# triggerbox.net
KiCad netlist of a schematic drawn in Altium Designer
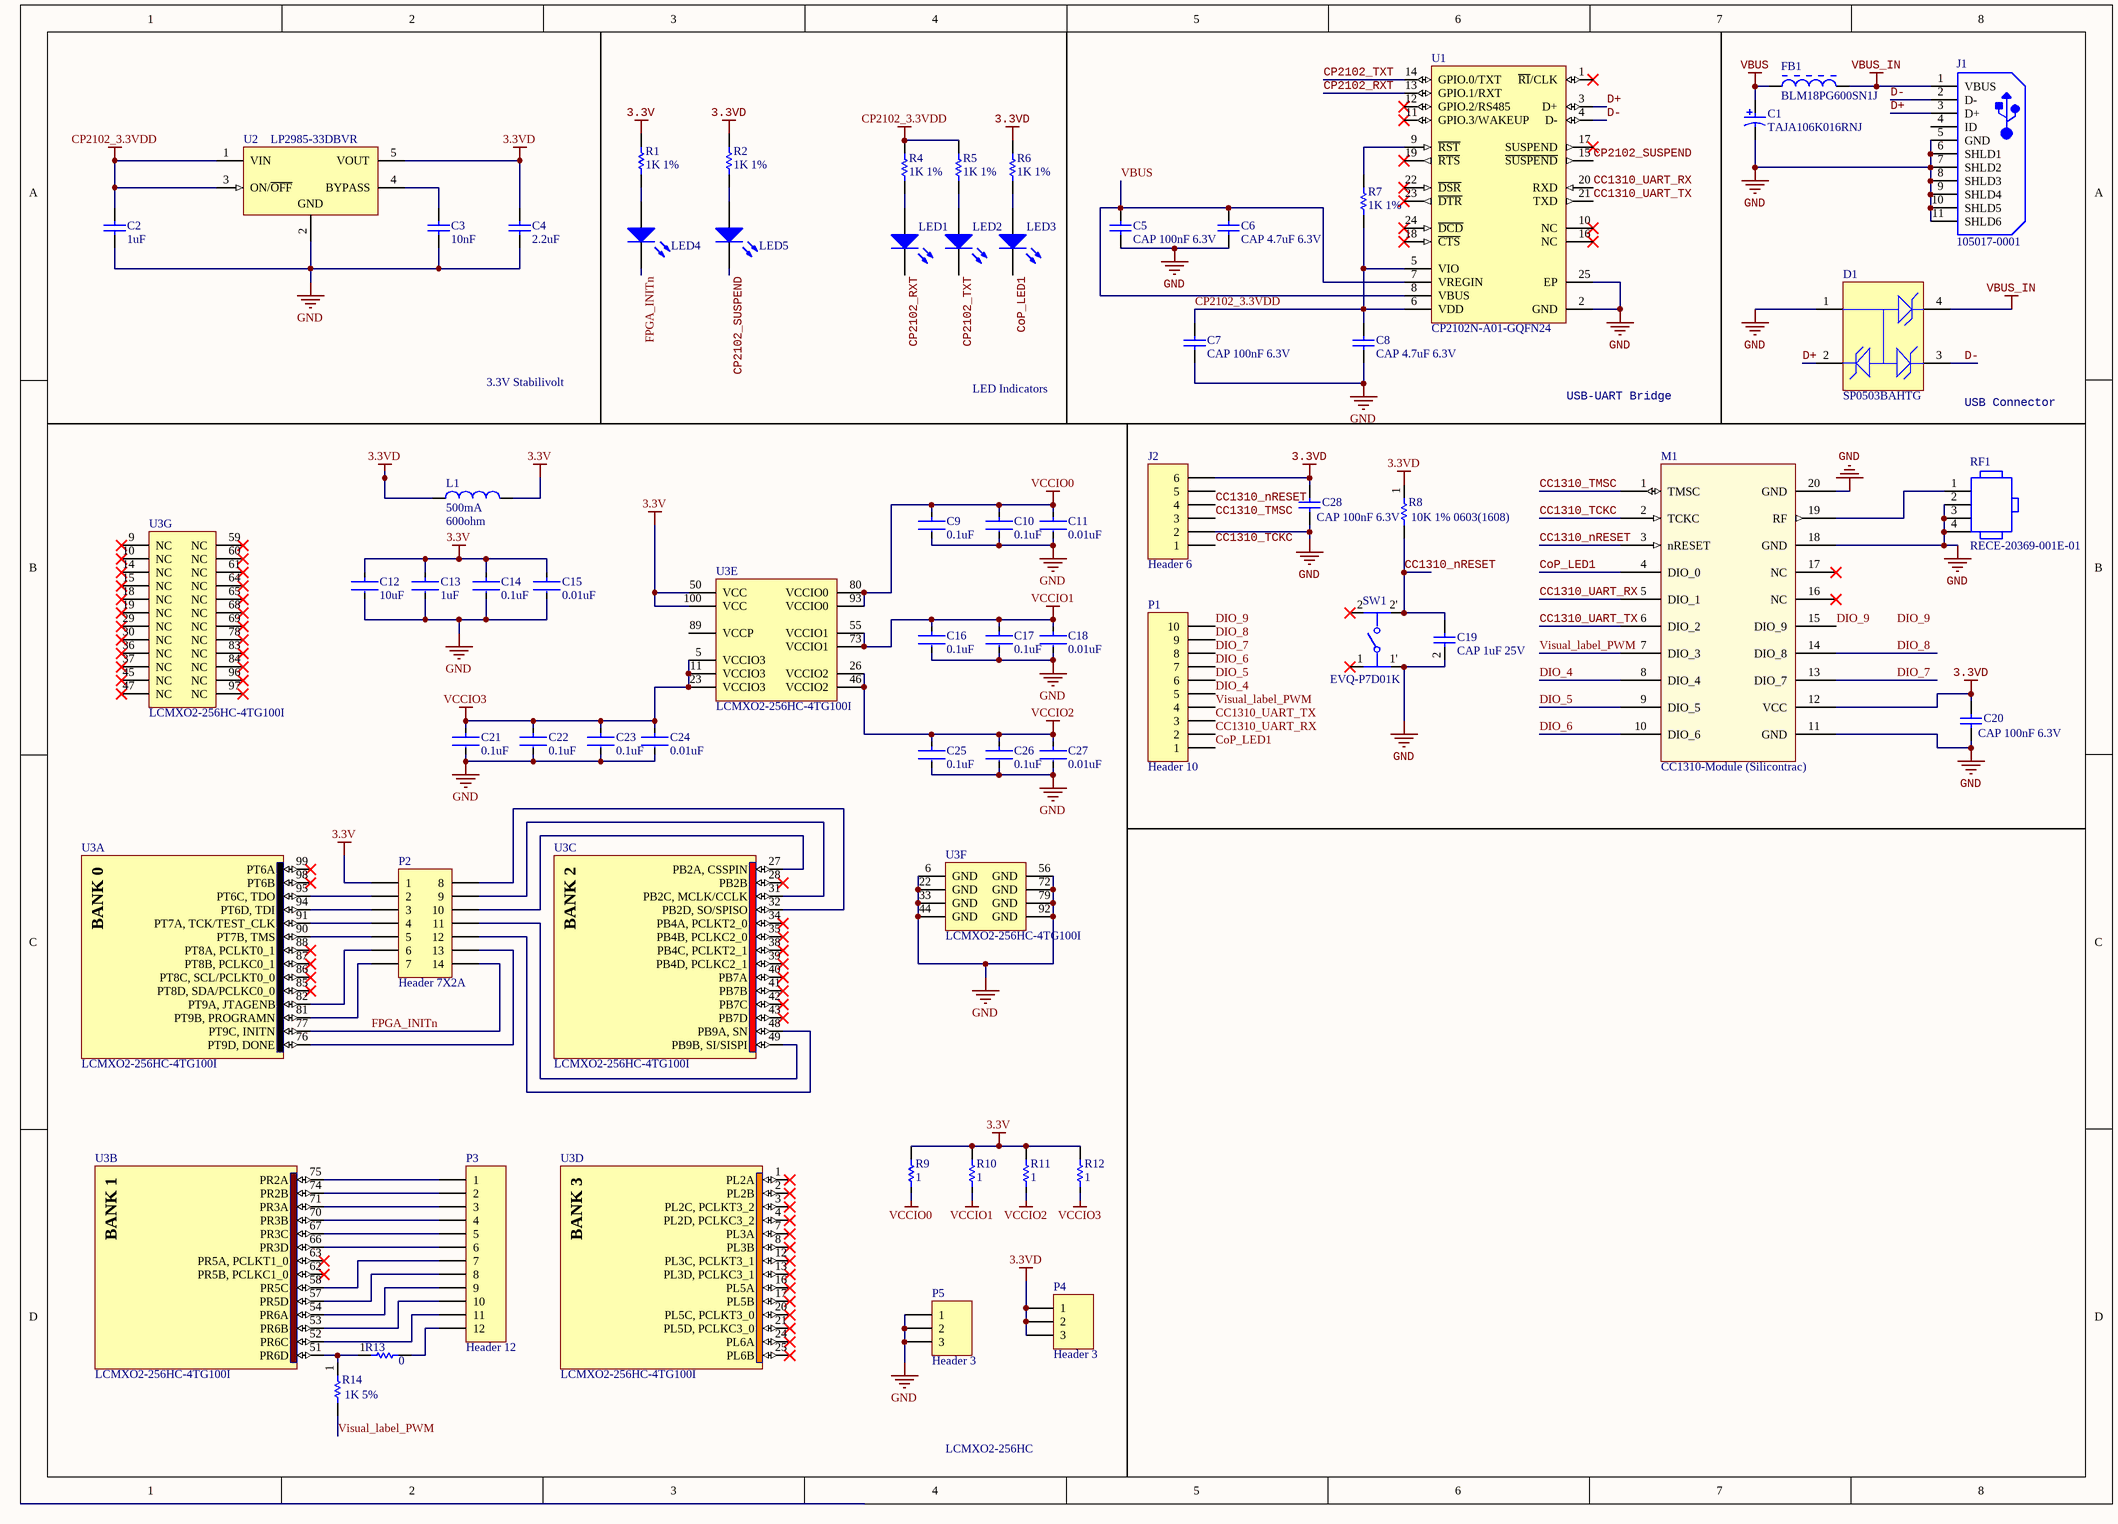
[diagram p0: triggerbox.SchDoc]

(export (version "E")
  (design (tool "Eeschema 10.0.6"))
  (components
    (comp (ref "C1")
      (value "TAJA106K016RNJ")
      (footprint "CAPMP3217X18-T_V")
      (description "Standard Tantalum, 10 uF, +/- 10%, 16 V, -55 to 125 degC, 2-Pin SMD (1206), RoHS, Tape and Reel")
      (libsource (lib "Altium Content Vault") (part "CAP-P-2"))
    )
    (comp (ref "C2")
      (value "1uF")
      (footprint "CAPC0603(1608)55_N")
      (description "CAP 4.7uF 10V ±20% 0603 (1608 Metric) Thickness 0.55mm SMD")
      (fields (field (name "TOLERANCE") "Â±20%"))
      (libsource (lib "Altium Content Vault") (part "CAP"))
    )
    (comp (ref "C3")
      (value "10nF")
      (footprint "CAPC0603(1608)55_N")
      (description "CAP 4.7uF 10V ±20% 0603 (1608 Metric) Thickness 0.55mm SMD")
      (fields (field (name "TOLERANCE") "Â±20%"))
      (libsource (lib "Altium Content Vault") (part "CAP"))
    )
    (comp (ref "C4")
      (value "2.2uF")
      (footprint "CAPC0603(1608)55_N")
      (description "CAP 4.7uF 10V ±20% 0603 (1608 Metric) Thickness 0.55mm SMD")
      (fields (field (name "TOLERANCE") "Â±20%"))
      (libsource (lib "Altium Content Vault") (part "CAP"))
    )
    (comp (ref "C5")
      (value "CAP 100nF 6.3V")
      (footprint "CAPC0603(1608)100_N")
      (description "CAP 100nF 6.3V ±5% 0603 (1608 Metric) Thickness 1mm SMD")
      (fields (field (name "TOLERANCE") "Â±5%"))
      (libsource (lib "Altium Content Vault") (part "CAP"))
    )
    (comp (ref "C6")
      (value "CAP 4.7uF 6.3V")
      (footprint "CAPC0603(1608)100_N")
      (description "CAP 4.7uF 6.3V ±20% 0603 (1608 Metric) Thickness 1mm SMD")
      (fields (field (name "TOLERANCE") "Â±20%"))
      (libsource (lib "Altium Content Vault") (part "CAP"))
    )
    (comp (ref "C7")
      (value "CAP 100nF 6.3V")
      (footprint "CAPC0603(1608)100_N")
      (description "CAP 100nF 6.3V ±5% 0603 (1608 Metric) Thickness 1mm SMD")
      (fields (field (name "TOLERANCE") "Â±5%"))
      (libsource (lib "Altium Content Vault") (part "CAP"))
    )
    (comp (ref "C8")
      (value "CAP 4.7uF 6.3V")
      (footprint "CAPC0603(1608)100_N")
      (description "CAP 4.7uF 6.3V ±20% 0603 (1608 Metric) Thickness 1mm SMD")
      (fields (field (name "TOLERANCE") "Â±20%"))
      (libsource (lib "Altium Content Vault") (part "CAP"))
    )
    (comp (ref "C9")
      (value "0.1uF")
      (footprint "FP-GRM155-0_05-IPC_A")
      (description "CAP CER 0.1UF 10V X5R 0402")
      (fields (field (name "VOLTAGE") "10V") (field (name "TOLERANCE") "10%"))
      (libsource (lib "Altium Content Vault") (part "02cd4be3c70576c341d710602a673aa"))
    )
    (comp (ref "C10")
      (value "0.1uF")
      (footprint "FP-GRM155-0_05-IPC_A")
      (description "CAP CER 0.1UF 10V X5R 0402")
      (fields (field (name "VOLTAGE") "10V") (field (name "TOLERANCE") "10%"))
      (libsource (lib "Altium Content Vault") (part "02cd4be3c70576c341d710602a673aa"))
    )
    (comp (ref "C11")
      (value "0.01uF")
      (footprint "FP-GRM155-0_05-IPC_A")
      (description "CAP CER 0.01UF 10V X5R 0402")
      (fields (field (name "VOLTAGE") "10V") (field (name "TOLERANCE") "10%"))
      (libsource (lib "Altium Content Vault") (part "02cd4be3c70576c341d710602a673aa"))
    )
    (comp (ref "C12")
      (value "10uF")
      (footprint "FP-GRM155-0_05-IPC_A")
      (description "CAP CER 0.1UF 10V X5R 0402")
      (fields (field (name "VOLTAGE") "10V") (field (name "TOLERANCE") "10%"))
      (libsource (lib "Altium Content Vault") (part "02cd4be3c70576c341d710602a673aa"))
    )
    (comp (ref "C13")
      (value "1uF")
      (footprint "FP-GRM155-0_05-IPC_A")
      (description "CAP CER 0.1UF 10V X5R 0402")
      (fields (field (name "VOLTAGE") "10V") (field (name "TOLERANCE") "10%"))
      (libsource (lib "Altium Content Vault") (part "02cd4be3c70576c341d710602a673aa"))
    )
    (comp (ref "C14")
      (value "0.1uF")
      (footprint "FP-GRM155-0_05-IPC_A")
      (description "CAP CER 0.1UF 10V X5R 0402")
      (fields (field (name "VOLTAGE") "10V") (field (name "TOLERANCE") "10%"))
      (libsource (lib "Altium Content Vault") (part "02cd4be3c70576c341d710602a673aa"))
    )
    (comp (ref "C15")
      (value "0.01uF")
      (footprint "FP-GRM155-0_05-IPC_A")
      (description "CAP CER 0.1UF 10V X5R 0402")
      (fields (field (name "VOLTAGE") "10V") (field (name "TOLERANCE") "10%"))
      (libsource (lib "Altium Content Vault") (part "02cd4be3c70576c341d710602a673aa"))
    )
    (comp (ref "C16")
      (value "0.1uF")
      (footprint "FP-GRM155-0_05-IPC_A")
      (description "CAP CER 0.1UF 10V X5R 0402")
      (fields (field (name "VOLTAGE") "10V") (field (name "TOLERANCE") "10%"))
      (libsource (lib "Altium Content Vault") (part "02cd4be3c70576c341d710602a673aa"))
    )
    (comp (ref "C17")
      (value "0.1uF")
      (footprint "FP-GRM155-0_05-IPC_A")
      (description "CAP CER 0.1UF 10V X5R 0402")
      (fields (field (name "VOLTAGE") "10V") (field (name "TOLERANCE") "10%"))
      (libsource (lib "Altium Content Vault") (part "02cd4be3c70576c341d710602a673aa"))
    )
    (comp (ref "C18")
      (value "0.01uF")
      (footprint "FP-GRM155-0_05-IPC_A")
      (description "CAP CER 0.01UF 10V X5R 0402")
      (fields (field (name "VOLTAGE") "10V") (field (name "TOLERANCE") "10%"))
      (libsource (lib "Altium Content Vault") (part "02cd4be3c70576c341d710602a673aa"))
    )
    (comp (ref "C19")
      (value "CAP 1uF 25V")
      (footprint "CAPC0603(1608)100_N")
      (description "CAP 1uF 25V ±20% 0603 (1608 Metric) Thickness 1mm SMD")
      (fields (field (name "TOLERANCE") "Â±20%"))
      (libsource (lib "") (part "CAP_1"))
    )
    (comp (ref "C20")
      (value "CAP 100nF 6.3V")
      (footprint "CAPC0603(1608)100_N")
      (description "CAP 100nF 6.3V ±10% 0603 (1608 Metric) Thickness 1mm SMD")
      (fields (field (name "TOLERANCE") "Â±10%"))
      (libsource (lib "Altium Content Vault") (part "CAP"))
    )
    (comp (ref "C21")
      (value "0.1uF")
      (footprint "FP-GRM155-0_05-IPC_A")
      (description "CAP CER 0.1UF 10V X5R 0402")
      (fields (field (name "VOLTAGE") "10V") (field (name "TOLERANCE") "10%"))
      (libsource (lib "Altium Content Vault") (part "02cd4be3c70576c341d710602a673aa"))
    )
    (comp (ref "C22")
      (value "0.1uF")
      (footprint "FP-GRM155-0_05-IPC_A")
      (description "CAP CER 0.1UF 10V X5R 0402")
      (fields (field (name "VOLTAGE") "10V") (field (name "TOLERANCE") "10%"))
      (libsource (lib "Altium Content Vault") (part "02cd4be3c70576c341d710602a673aa"))
    )
    (comp (ref "C23")
      (value "0.1uF")
      (footprint "FP-GRM155-0_05-IPC_A")
      (description "CAP CER 0.1UF 10V X5R 0402")
      (fields (field (name "VOLTAGE") "10V") (field (name "TOLERANCE") "10%"))
      (libsource (lib "Altium Content Vault") (part "02cd4be3c70576c341d710602a673aa"))
    )
    (comp (ref "C24")
      (value "0.01uF")
      (footprint "FP-GRM155-0_05-IPC_A")
      (description "CAP CER 0.01UF 10V X5R 0402")
      (fields (field (name "VOLTAGE") "10V") (field (name "TOLERANCE") "10%"))
      (libsource (lib "Altium Content Vault") (part "02cd4be3c70576c341d710602a673aa"))
    )
    (comp (ref "C25")
      (value "0.1uF")
      (footprint "FP-GRM155-0_05-IPC_A")
      (description "CAP CER 0.1UF 10V X5R 0402")
      (fields (field (name "VOLTAGE") "10V") (field (name "TOLERANCE") "10%"))
      (libsource (lib "Altium Content Vault") (part "02cd4be3c70576c341d710602a673aa"))
    )
    (comp (ref "C26")
      (value "0.1uF")
      (footprint "FP-GRM155-0_05-IPC_A")
      (description "CAP CER 0.1UF 10V X5R 0402")
      (fields (field (name "VOLTAGE") "10V") (field (name "TOLERANCE") "10%"))
      (libsource (lib "Altium Content Vault") (part "02cd4be3c70576c341d710602a673aa"))
    )
    (comp (ref "C27")
      (value "0.01uF")
      (footprint "FP-GRM155-0_05-IPC_A")
      (description "CAP CER 0.01UF 10V X5R 0402")
      (fields (field (name "VOLTAGE") "10V") (field (name "TOLERANCE") "10%"))
      (libsource (lib "Altium Content Vault") (part "02cd4be3c70576c341d710602a673aa"))
    )
    (comp (ref "C28")
      (value "CAP 100nF 6.3V")
      (footprint "CAPC0603(1608)100_N")
      (description "CAP 100nF 6.3V ±10% 0603 (1608 Metric) Thickness 1mm SMD")
      (fields (field (name "TOLERANCE") "Â±10%"))
      (libsource (lib "Altium Content Vault") (part "CAP"))
    )
    (comp (ref "D1")
      (value "SP0503BAHTG")
      (footprint "LFUS-SOT143-4_V")
      (description "TVS Diode Array, 30 pF, 30 KV, -40 to 85 degC, 4-Pin SOT143, RoHS, Tape and Reel")
      (fields (field (name "MANUFACTURER") "Littelfuse"))
      (libsource (lib "Altium Content Vault") (part "LFUS-SP0503BAHTG-SOT143-4"))
    )
    (comp (ref "FB1")
      (value "BLM18PG600SN1J")
      (footprint "MURA-BLM18PG_KG-CHIP-2_V2")
      (fields (field (name "MANUFACTURER") "Murata"))
      (libsource (lib "Altium Content Vault") (part "MURA-FB-2"))
    )
    (comp (ref "J1")
      (value "105017-0001")
      (footprint "USB-MICRO-B_V")
      (fields (field (name "MANUFACTURER") "Molex"))
      (libsource (lib "Altium Content Vault") (part "USB-5-6SHLD"))
    )
    (comp (ref "J2")
      (value "Header 6")
      (footprint "GH-1.25-WS-6P")
      (description "Header, 6-Pin")
      (fields (field (name "PUBLISHER") "Altium Limited"))
      (libsource (lib "Miscellaneous Connectors") (part "Header 6"))
    )
    (comp (ref "L1")
      (value "500mA")
      (footprint "0402-A")
      (description "Inductor")
      (fields (field (name "ALTIUM_VALUE") "600ohm") (field (name "PUBLISHER") "Altium Limited"))
      (libsource (lib "Miscellaneous Devices") (part "Inductor"))
    )
    (comp (ref "LED1")
      (value "150060BS75000")
      (footprint "0603_A")
      (description "SMD mono-color Chip LED, WL-SMCW, Blue")
      (fields (field (name "MANUFACTURER") "Wuerth Elektronik"))
      (libsource (lib "Altium Content Vault") (part "WE-LED_K1A2-2"))
    )
    (comp (ref "LED2")
      (value "150060BS75000")
      (footprint "0603_A")
      (description "SMD mono-color Chip LED, WL-SMCW, Blue")
      (fields (field (name "MANUFACTURER") "Wuerth Elektronik"))
      (libsource (lib "Altium Content Vault") (part "WE-LED_K1A2-2"))
    )
    (comp (ref "LED3")
      (value "150060BS75000")
      (footprint "0603_A")
      (description "SMD mono-color Chip LED, WL-SMCW, Blue")
      (fields (field (name "MANUFACTURER") "Wuerth Elektronik"))
      (libsource (lib "Altium Content Vault") (part "WE-LED_K1A2-2"))
    )
    (comp (ref "LED4")
      (value "150060BS75000")
      (footprint "0603_A")
      (description "SMD mono-color Chip LED, WL-SMCW, Blue")
      (fields (field (name "MANUFACTURER") "Wuerth Elektronik"))
      (libsource (lib "Altium Content Vault") (part "WE-LED_K1A2-2"))
    )
    (comp (ref "LED5")
      (value "150060BS75000")
      (footprint "0603_A")
      (description "SMD mono-color Chip LED, WL-SMCW, Blue")
      (fields (field (name "MANUFACTURER") "Wuerth Elektronik"))
      (libsource (lib "Altium Content Vault") (part "WE-LED_K1A2-2"))
    )
    (comp (ref "M1")
      (value "CC1310-Module (Silicontrac)")
      (footprint "CC1310ZTR4-GC")
      (libsource (lib "NanoEEG_v2_MCU") (part "CC1310-MOD"))
    )
    (comp (ref "P1")
      (value "Header 10")
      (footprint "HDR1X10")
      (description "Header, 10-Pin")
      (fields (field (name "PUBLISHER") "Altium Limited"))
      (libsource (lib "Miscellaneous Connectors") (part "Header 10"))
    )
    (comp (ref "P2")
      (value "Header 7X2A")
      (footprint "HDR2X7_CEN")
      (description "Header, 7-Pin, Dual row")
      (fields (field (name "PUBLISHER") "Altium Limited"))
      (libsource (lib "Miscellaneous Connectors") (part "Header 7X2A"))
    )
    (comp (ref "P3")
      (value "Header 12")
      (footprint "HDR1X12")
      (description "Header, 12-Pin")
      (fields (field (name "PUBLISHER") "Altium Limited"))
      (libsource (lib "Miscellaneous Connectors") (part "Header 12"))
    )
    (comp (ref "P4")
      (value "Header 3")
      (footprint "HDR1X3")
      (description "Header, 3-Pin")
      (fields (field (name "PUBLISHER") "Altium Limited"))
      (libsource (lib "Miscellaneous Connectors") (part "Header 3"))
    )
    (comp (ref "P5")
      (value "Header 3")
      (footprint "HDR1X3")
      (description "Header, 3-Pin")
      (fields (field (name "PUBLISHER") "Altium Limited"))
      (libsource (lib "Miscellaneous Connectors") (part "Header 3"))
    )
    (comp (ref "R1")
      (value "1K 1%")
      (footprint "RESC0603(1608)_N")
      (description "1K 0.1W 1% 0603 (1608 Metric)  SMD")
      (fields (field (name "TOLERANCE") "1 %") (field (name "POWER") "0.1 W"))
      (libsource (lib "Altium Content Vault") (part "RES"))
    )
    (comp (ref "R2")
      (value "1K 1%")
      (footprint "RESC0603(1608)_N")
      (description "1K 0.1W 1% 0603 (1608 Metric)  SMD")
      (fields (field (name "TOLERANCE") "1 %") (field (name "POWER") "0.1 W"))
      (libsource (lib "Altium Content Vault") (part "RES"))
    )
    (comp (ref "R4")
      (value "1K 1%")
      (footprint "RESC0603(1608)_N")
      (description "1K 0.1W 1% 0603 (1608 Metric)  SMD")
      (fields (field (name "TOLERANCE") "1 %") (field (name "POWER") "0.1 W"))
      (libsource (lib "Altium Content Vault") (part "RES"))
    )
    (comp (ref "R5")
      (value "1K 1%")
      (footprint "RESC0603(1608)_N")
      (description "1K 0.1W 1% 0603 (1608 Metric)  SMD")
      (fields (field (name "TOLERANCE") "1 %") (field (name "POWER") "0.1 W"))
      (libsource (lib "Altium Content Vault") (part "RES"))
    )
    (comp (ref "R6")
      (value "1K 1%")
      (footprint "RESC0603(1608)_N")
      (description "1K 0.1W 1% 0603 (1608 Metric)  SMD")
      (fields (field (name "TOLERANCE") "1 %") (field (name "POWER") "0.1 W"))
      (libsource (lib "Altium Content Vault") (part "RES"))
    )
    (comp (ref "R7")
      (value "1K 1%")
      (footprint "RESC0603(1608)_N")
      (description "1K 0.1W 1% 0603 (1608 Metric)  SMD")
      (fields (field (name "TOLERANCE") "1 %") (field (name "POWER") "0.1 W"))
      (libsource (lib "NanoEEG_v2_MCU") (part "CMP-1012-00510-1"))
    )
    (comp (ref "R8")
      (value "10K 1% 0603(1608)")
      (footprint "RESC0603(1608)_N")
      (description "10K 0.1W 1% 0603 (1608 Metric)  SMD")
      (fields (field (name "POWER") "0.1 W") (field (name "TOLERANCE") "1 %"))
      (libsource (lib "") (part "RES_1"))
    )
    (comp (ref "R9")
      (value "1")
      (footprint "RESC0603(1608)_N")
      (description "1K 0.1W 1% 0603 (1608 Metric)  SMD")
      (fields (field (name "TOLERANCE") "1 %") (field (name "POWER") "0.1 W"))
      (libsource (lib "Altium Content Vault") (part "RES"))
    )
    (comp (ref "R10")
      (value "1")
      (footprint "RESC0603(1608)_N")
      (description "1K 0.1W 1% 0603 (1608 Metric)  SMD")
      (fields (field (name "TOLERANCE") "1 %") (field (name "POWER") "0.1 W"))
      (libsource (lib "Altium Content Vault") (part "RES"))
    )
    (comp (ref "R11")
      (value "1")
      (footprint "RESC0603(1608)_N")
      (description "1K 0.1W 1% 0603 (1608 Metric)  SMD")
      (fields (field (name "TOLERANCE") "1 %") (field (name "POWER") "0.1 W"))
      (libsource (lib "Altium Content Vault") (part "RES"))
    )
    (comp (ref "R12")
      (value "1")
      (footprint "RESC0603(1608)_N")
      (description "1K 0.1W 1% 0603 (1608 Metric)  SMD")
      (fields (field (name "TOLERANCE") "1 %") (field (name "POWER") "0.1 W"))
      (libsource (lib "Altium Content Vault") (part "RES"))
    )
    (comp (ref "R13")
      (value "0")
      (footprint "RESC0603(1608)_N")
      (description "10K 0.1W 1% 0603 (1608 Metric)  SMD")
      (fields (field (name "POWER") "0.1 W") (field (name "TOLERANCE") "1 %"))
      (libsource (lib "") (part "RES_1"))
    )
    (comp (ref "R14")
      (value "1K 5%")
      (footprint "RESC0603(1608)_N")
      (description "10K 0.1W 1% 0603 (1608 Metric)  SMD")
      (fields (field (name "POWER") "0.1 W") (field (name "TOLERANCE") "1 %"))
      (libsource (lib "") (part "RES_1"))
    )
    (comp (ref "RF1")
      (value "RECE-20369-001E-01")
      (footprint "IPEX_MHF_I")
      (description "RF Connector, Onboard Receptacle, IPEX MHFIII")
      (fields (field (name "MANUFACTURER") "Taoglas"))
      (libsource (lib "Miscellaneous Connectors") (part "TG-RECE-20369-001E-01-4"))
    )
    (comp (ref "SW1")
      (value "EVQ-P7D01K")
      (footprint "FP-EVQ-P7D01K-MFG")
      (description "SWITCH TACTILE SPST-NO 0.05A 12V")
      (libsource (lib "Altium Content Vault") (part "81ddb76e3b1ae09a591072546e26dfd"))
    )
    (comp (ref "U1")
      (value "CP2102N-A01-GQFN24")
      (footprint "SLAB-QFN-24-2550x2550TP_A_V")
      (description "USBXpress(TM) Family, 4 GPIOs, 2.2 to 3.6 V, -40 to 85 degC, 24-Pin QFN, RoHS")
      (fields (field (name "MANUFACTURER") "Silicon Labs"))
      (libsource (lib "NanoEEG_v2_MCU") (part "SLAB-CP2102N-QFN-24"))
    )
    (comp (ref "U2")
      (value "LP2985-33DBVR")
      (footprint "DBV0005A_M")
      (fields (field (name "MANUFACTURER") "Texas Instruments"))
      (libsource (lib "Altium Content Vault") (part "TI-LP2985_A-10DBV5"))
    )
    (comp (ref "U3")
      (value "LCMXO2-256HC-4TG100I")
      (footprint "TQFP100_N")
      (libsource (lib "Altium Content Vault") (part "PLD-LTMXO2-256-TQ100"))
    )
  )
  (nets
    (net (code "1") (name "/CC1310_TCKC") (class "Default")
      (node (ref "J2") (pin "1") (pinfunction "1_1") (pintype "passive"))
      (node (ref "M1") (pin "2") (pinfunction "TCKC_2") (pintype "input"))
    )
    (net (code "2") (name "/CC1310_TMSC") (class "Default")
      (node (ref "J2") (pin "3") (pinfunction "3_3") (pintype "passive"))
      (node (ref "M1") (pin "1") (pinfunction "TMSC_1") (pintype "bidirectional"))
    )
    (net (code "3") (name "/CC1310_UART_RX") (class "Default")
      (node (ref "M1") (pin "5") (pinfunction "DIO_1_5") (pintype "passive"))
      (node (ref "P1") (pin "2") (pinfunction "2_2") (pintype "passive"))
      (node (ref "U1") (pin "20") (pinfunction "RXD_20") (pintype "input"))
    )
    (net (code "4") (name "/CC1310_UART_TX") (class "Default")
      (node (ref "M1") (pin "6") (pinfunction "DIO_2_6") (pintype "passive"))
      (node (ref "P1") (pin "3") (pinfunction "3_3") (pintype "passive"))
      (node (ref "U1") (pin "21") (pinfunction "TXD_21") (pintype "output"))
    )
    (net (code "5") (name "/CC1310_nRESET") (class "Default")
      (node (ref "C19") (pin "1") (pinfunction "1_1") (pintype "passive"))
      (node (ref "J2") (pin "4") (pinfunction "4_4") (pintype "passive"))
      (node (ref "M1") (pin "3") (pinfunction "nRESET_3") (pintype "input"))
      (node (ref "R8") (pin "2") (pinfunction "2_2") (pintype "passive"))
      (node (ref "SW1") (pin "2'") (pinfunction "2'_2'") (pintype "passive"))
    )
    (net (code "6") (name "/CP2102_RXT") (class "Default")
      (node (ref "LED1") (pin "1") (pinfunction "K_1") (pintype "passive"))
      (node (ref "U1") (pin "13") (pinfunction "GPIO.1/RXT_13") (pintype "bidirectional"))
    )
    (net (code "7") (name "/CP2102_SUSPEND") (class "Default")
      (node (ref "LED5") (pin "1") (pinfunction "K_1") (pintype "passive"))
      (node (ref "U1") (pin "15") (pinfunction "~{SUSPEND}_15") (pintype "output"))
    )
    (net (code "8") (name "/CP2102_TXT") (class "Default")
      (node (ref "LED2") (pin "1") (pinfunction "K_1") (pintype "passive"))
      (node (ref "U1") (pin "14") (pinfunction "GPIO.0/TXT_14") (pintype "bidirectional"))
    )
    (net (code "9") (name "/CoP_LED1") (class "Default")
      (node (ref "LED3") (pin "1") (pinfunction "K_1") (pintype "passive"))
      (node (ref "M1") (pin "4") (pinfunction "DIO_0_4") (pintype "passive"))
      (node (ref "P1") (pin "1") (pinfunction "1_1") (pintype "passive"))
    )
    (net (code "10") (name "/D+") (class "Default")
      (node (ref "D1") (pin "2") (pinfunction "2_2") (pintype "passive"))
      (node (ref "J1") (pin "3") (pinfunction "D+_3") (pintype "passive"))
      (node (ref "U1") (pin "3") (pinfunction "D+_3") (pintype "bidirectional"))
    )
    (net (code "11") (name "/D-") (class "Default")
      (node (ref "D1") (pin "3") (pinfunction "3_3") (pintype "passive"))
      (node (ref "J1") (pin "2") (pinfunction "D-_2") (pintype "passive"))
      (node (ref "U1") (pin "4") (pinfunction "D-_4") (pintype "bidirectional"))
    )
    (net (code "12") (name "/DIO_4") (class "Default")
      (node (ref "M1") (pin "8") (pinfunction "DIO_4_8") (pintype "passive"))
      (node (ref "P1") (pin "5") (pinfunction "5_5") (pintype "passive"))
    )
    (net (code "13") (name "/DIO_5") (class "Default")
      (node (ref "M1") (pin "9") (pinfunction "DIO_5_9") (pintype "passive"))
      (node (ref "P1") (pin "6") (pinfunction "6_6") (pintype "passive"))
    )
    (net (code "14") (name "/DIO_6") (class "Default")
      (node (ref "M1") (pin "10") (pinfunction "DIO_6_10") (pintype "passive"))
      (node (ref "P1") (pin "7") (pinfunction "7_7") (pintype "passive"))
    )
    (net (code "15") (name "/DIO_7") (class "Default")
      (node (ref "M1") (pin "13") (pinfunction "DIO_7_13") (pintype "passive"))
      (node (ref "P1") (pin "8") (pinfunction "8_8") (pintype "passive"))
    )
    (net (code "16") (name "/DIO_8") (class "Default")
      (node (ref "M1") (pin "14") (pinfunction "DIO_8_14") (pintype "passive"))
      (node (ref "P1") (pin "9") (pinfunction "9_9") (pintype "passive"))
    )
    (net (code "17") (name "/DIO_9") (class "Default")
      (node (ref "M1") (pin "15") (pinfunction "DIO_9_15") (pintype "passive"))
      (node (ref "P1") (pin "10") (pinfunction "10_10") (pintype "passive"))
    )
    (net (code "18") (name "/FPGA_INITn") (class "Default")
      (node (ref "LED4") (pin "1") (pinfunction "K_1") (pintype "passive"))
      (node (ref "P2") (pin "14") (pinfunction "14_14") (pintype "passive"))
      (node (ref "U3") (pin "77") (pinfunction "PT9C,_INITN_77") (pintype "bidirectional"))
    )
    (net (code "19") (name "/Visual_label_PWM") (class "Default")
      (node (ref "M1") (pin "7") (pinfunction "DIO_3_7") (pintype "passive"))
      (node (ref "P1") (pin "4") (pinfunction "4_4") (pintype "passive"))
      (node (ref "R14") (pin "2") (pinfunction "2_2") (pintype "passive"))
    )
    (net (code "20") (name "3.3V") (class "Default")
      (node (ref "C12") (pin "1") (pinfunction "1_1") (pintype "passive"))
      (node (ref "C13") (pin "1") (pinfunction "1_1") (pintype "passive"))
      (node (ref "C14") (pin "1") (pinfunction "1_1") (pintype "passive"))
      (node (ref "C15") (pin "1") (pinfunction "1_1") (pintype "passive"))
      (node (ref "L1") (pin "2") (pinfunction "2_2") (pintype "passive"))
      (node (ref "P2") (pin "1") (pinfunction "1_1") (pintype "passive"))
      (node (ref "R1") (pin "2") (pinfunction "2_2") (pintype "passive"))
      (node (ref "R10") (pin "2") (pinfunction "2_2") (pintype "passive"))
      (node (ref "R11") (pin "2") (pinfunction "2_2") (pintype "passive"))
      (node (ref "R12") (pin "2") (pinfunction "2_2") (pintype "passive"))
      (node (ref "R9") (pin "2") (pinfunction "2_2") (pintype "passive"))
      (node (ref "U3") (pin "100") (pinfunction "VCC_100") (pintype "power_in"))
      (node (ref "U3") (pin "50") (pinfunction "VCC_50") (pintype "power_in"))
    )
    (net (code "21") (name "3.3VD") (class "Default")
      (node (ref "C20") (pin "2") (pinfunction "2_2") (pintype "passive"))
      (node (ref "C28") (pin "2") (pinfunction "2_2") (pintype "passive"))
      (node (ref "C4") (pin "2") (pinfunction "2_2") (pintype "passive"))
      (node (ref "J2") (pin "6") (pinfunction "6_6") (pintype "passive"))
      (node (ref "L1") (pin "1") (pinfunction "1_1") (pintype "passive"))
      (node (ref "M1") (pin "12") (pinfunction "VCC_12") (pintype "power_in"))
      (node (ref "P4") (pin "1") (pinfunction "1_1") (pintype "passive"))
      (node (ref "P4") (pin "2") (pinfunction "2_2") (pintype "passive"))
      (node (ref "P4") (pin "3") (pinfunction "3_3") (pintype "passive"))
      (node (ref "R2") (pin "2") (pinfunction "2_2") (pintype "passive"))
      (node (ref "R6") (pin "2") (pinfunction "2_2") (pintype "passive"))
      (node (ref "R8") (pin "1") (pinfunction "1_1") (pintype "passive"))
      (node (ref "U2") (pin "5") (pinfunction "VOUT_5") (pintype "power_in"))
    )
    (net (code "22") (name "CP2102_3.3VDD") (class "Default")
      (node (ref "C2") (pin "2") (pinfunction "2_2") (pintype "passive"))
      (node (ref "C7") (pin "2") (pinfunction "2_2") (pintype "passive"))
      (node (ref "C8") (pin "2") (pinfunction "2_2") (pintype "passive"))
      (node (ref "R4") (pin "2") (pinfunction "2_2") (pintype "passive"))
      (node (ref "R5") (pin "2") (pinfunction "2_2") (pintype "passive"))
      (node (ref "R7") (pin "1") (pinfunction "1_1") (pintype "passive"))
      (node (ref "U1") (pin "5") (pinfunction "VIO_5") (pintype "power_in"))
      (node (ref "U1") (pin "6") (pinfunction "VDD_6") (pintype "power_in"))
      (node (ref "U2") (pin "1") (pinfunction "VIN_1") (pintype "power_in"))
      (node (ref "U2") (pin "3") (pinfunction "ON/~{OFF}_3") (pintype "input"))
    )
    (net (code "23") (name "GND") (class "Default")
      (node (ref "C1") (pin "2") (pinfunction "2_2") (pintype "passive"))
      (node (ref "C10") (pin "2") (pinfunction "2_2") (pintype "passive"))
      (node (ref "C11") (pin "2") (pinfunction "2_2") (pintype "passive"))
      (node (ref "C12") (pin "2") (pinfunction "2_2") (pintype "passive"))
      (node (ref "C13") (pin "2") (pinfunction "2_2") (pintype "passive"))
      (node (ref "C14") (pin "2") (pinfunction "2_2") (pintype "passive"))
      (node (ref "C15") (pin "2") (pinfunction "2_2") (pintype "passive"))
      (node (ref "C16") (pin "2") (pinfunction "2_2") (pintype "passive"))
      (node (ref "C17") (pin "2") (pinfunction "2_2") (pintype "passive"))
      (node (ref "C18") (pin "2") (pinfunction "2_2") (pintype "passive"))
      (node (ref "C19") (pin "2") (pinfunction "2_2") (pintype "passive"))
      (node (ref "C2") (pin "1") (pinfunction "1_1") (pintype "passive"))
      (node (ref "C20") (pin "1") (pinfunction "1_1") (pintype "passive"))
      (node (ref "C21") (pin "2") (pinfunction "2_2") (pintype "passive"))
      (node (ref "C22") (pin "2") (pinfunction "2_2") (pintype "passive"))
      (node (ref "C23") (pin "2") (pinfunction "2_2") (pintype "passive"))
      (node (ref "C24") (pin "2") (pinfunction "2_2") (pintype "passive"))
      (node (ref "C25") (pin "2") (pinfunction "2_2") (pintype "passive"))
      (node (ref "C26") (pin "2") (pinfunction "2_2") (pintype "passive"))
      (node (ref "C27") (pin "2") (pinfunction "2_2") (pintype "passive"))
      (node (ref "C28") (pin "1") (pinfunction "1_1") (pintype "passive"))
      (node (ref "C3") (pin "1") (pinfunction "1_1") (pintype "passive"))
      (node (ref "C4") (pin "1") (pinfunction "1_1") (pintype "passive"))
      (node (ref "C5") (pin "1") (pinfunction "1_1") (pintype "passive"))
      (node (ref "C6") (pin "1") (pinfunction "1_1") (pintype "passive"))
      (node (ref "C7") (pin "1") (pinfunction "1_1") (pintype "passive"))
      (node (ref "C8") (pin "1") (pinfunction "1_1") (pintype "passive"))
      (node (ref "C9") (pin "2") (pinfunction "2_2") (pintype "passive"))
      (node (ref "D1") (pin "1") (pinfunction "1_1") (pintype "passive"))
      (node (ref "J1") (pin "10") (pinfunction "SHLD5_10") (pintype "passive"))
      (node (ref "J1") (pin "11") (pinfunction "SHLD6_11") (pintype "passive"))
      (node (ref "J1") (pin "5") (pinfunction "GND_5") (pintype "passive"))
      (node (ref "J1") (pin "6") (pinfunction "SHLD1_6") (pintype "passive"))
      (node (ref "J1") (pin "7") (pinfunction "SHLD2_7") (pintype "passive"))
      (node (ref "J1") (pin "8") (pinfunction "SHLD3_8") (pintype "passive"))
      (node (ref "J1") (pin "9") (pinfunction "SHLD4_9") (pintype "passive"))
      (node (ref "J2") (pin "2") (pinfunction "2_2") (pintype "passive"))
      (node (ref "M1") (pin "11") (pinfunction "GND_11") (pintype "power_in"))
      (node (ref "M1") (pin "18") (pinfunction "GND_18") (pintype "power_in"))
      (node (ref "M1") (pin "20") (pinfunction "GND_20") (pintype "power_in"))
      (node (ref "P5") (pin "1") (pinfunction "1_1") (pintype "passive"))
      (node (ref "P5") (pin "2") (pinfunction "2_2") (pintype "passive"))
      (node (ref "P5") (pin "3") (pinfunction "3_3") (pintype "passive"))
      (node (ref "RF1") (pin "2") (pinfunction "2_2") (pintype "passive"))
      (node (ref "RF1") (pin "3") (pinfunction "3_3") (pintype "passive"))
      (node (ref "RF1") (pin "4") (pinfunction "4_4") (pintype "passive"))
      (node (ref "SW1") (pin "1'") (pinfunction "1'_1'") (pintype "passive"))
      (node (ref "U1") (pin "2") (pinfunction "GND_2") (pintype "power_in"))
      (node (ref "U1") (pin "25") (pinfunction "EP_25") (pintype "power_in"))
      (node (ref "U2") (pin "2") (pinfunction "GND_2") (pintype "power_in"))
      (node (ref "U3") (pin "22") (pinfunction "GND_22") (pintype "power_in"))
      (node (ref "U3") (pin "33") (pinfunction "GND_33") (pintype "power_in"))
      (node (ref "U3") (pin "44") (pinfunction "GND_44") (pintype "power_in"))
      (node (ref "U3") (pin "56") (pinfunction "GND_56") (pintype "power_in"))
      (node (ref "U3") (pin "6") (pinfunction "GND_6") (pintype "power_in"))
      (node (ref "U3") (pin "72") (pinfunction "GND_72") (pintype "power_in"))
      (node (ref "U3") (pin "79") (pinfunction "GND_79") (pintype "power_in"))
      (node (ref "U3") (pin "92") (pinfunction "GND_92") (pintype "power_in"))
    )
    (net (code "24") (name "Net-(LED1-A)") (class "Default")
      (node (ref "LED1") (pin "2") (pinfunction "A_2") (pintype "passive"))
      (node (ref "R4") (pin "1") (pinfunction "1_1") (pintype "passive"))
    )
    (net (code "25") (name "Net-(LED2-A)") (class "Default")
      (node (ref "LED2") (pin "2") (pinfunction "A_2") (pintype "passive"))
      (node (ref "R5") (pin "1") (pinfunction "1_1") (pintype "passive"))
    )
    (net (code "26") (name "Net-(LED3-A)") (class "Default")
      (node (ref "LED3") (pin "2") (pinfunction "A_2") (pintype "passive"))
      (node (ref "R6") (pin "1") (pinfunction "1_1") (pintype "passive"))
    )
    (net (code "27") (name "Net-(LED4-A)") (class "Default")
      (node (ref "LED4") (pin "2") (pinfunction "A_2") (pintype "passive"))
      (node (ref "R1") (pin "1") (pinfunction "1_1") (pintype "passive"))
    )
    (net (code "28") (name "Net-(LED5-A)") (class "Default")
      (node (ref "LED5") (pin "2") (pinfunction "A_2") (pintype "passive"))
      (node (ref "R2") (pin "1") (pinfunction "1_1") (pintype "passive"))
    )
    (net (code "29") (name "Net-(M1-RF)") (class "Default")
      (node (ref "M1") (pin "19") (pinfunction "RF_19") (pintype "output"))
      (node (ref "RF1") (pin "1") (pinfunction "1_1") (pintype "passive"))
    )
    (net (code "30") (name "Net-(P3-Pad12)") (class "Default")
      (node (ref "P3") (pin "12") (pinfunction "12_12") (pintype "passive"))
      (node (ref "R13") (pin "2") (pinfunction "2_2") (pintype "passive"))
    )
    (net (code "31") (name "Net-(U1-~{RST})") (class "Default")
      (node (ref "R7") (pin "2") (pinfunction "2_2") (pintype "passive"))
      (node (ref "U1") (pin "9") (pinfunction "~{RST}_9") (pintype "input"))
    )
    (net (code "32") (name "Net-(U2-BYPASS)") (class "Default")
      (node (ref "C3") (pin "2") (pinfunction "2_2") (pintype "passive"))
      (node (ref "U2") (pin "4") (pinfunction "BYPASS_4") (pintype "passive"))
    )
    (net (code "33") (name "Net-(U3A-PT6C,_TDO)") (class "Default")
      (node (ref "P2") (pin "2") (pinfunction "2_2") (pintype "passive"))
      (node (ref "U3") (pin "95") (pinfunction "PT6C,_TDO_95") (pintype "bidirectional"))
    )
    (net (code "34") (name "Net-(U3A-PT6D,_TDI)") (class "Default")
      (node (ref "P2") (pin "3") (pinfunction "3_3") (pintype "passive"))
      (node (ref "U3") (pin "94") (pinfunction "PT6D,_TDI_94") (pintype "bidirectional"))
    )
    (net (code "35") (name "Net-(U3A-PT7A,_TCK{slash}TEST_CLK)") (class "Default")
      (node (ref "P2") (pin "4") (pinfunction "4_4") (pintype "passive"))
      (node (ref "U3") (pin "91") (pinfunction "PT7A,_TCK/TEST_CLK_91") (pintype "bidirectional"))
    )
    (net (code "36") (name "Net-(U3A-PT7B,_TMS)") (class "Default")
      (node (ref "P2") (pin "5") (pinfunction "5_5") (pintype "passive"))
      (node (ref "U3") (pin "90") (pinfunction "PT7B,_TMS_90") (pintype "bidirectional"))
    )
    (net (code "37") (name "Net-(U3A-PT9A,_JTAGENB)") (class "Default")
      (node (ref "P2") (pin "6") (pinfunction "6_6") (pintype "passive"))
      (node (ref "U3") (pin "82") (pinfunction "PT9A,_JTAGENB_82") (pintype "bidirectional"))
    )
    (net (code "38") (name "Net-(U3A-PT9B,_PROGRAMN)") (class "Default")
      (node (ref "P2") (pin "7") (pinfunction "7_7") (pintype "passive"))
      (node (ref "U3") (pin "81") (pinfunction "PT9B,_PROGRAMN_81") (pintype "bidirectional"))
    )
    (net (code "39") (name "Net-(U3A-PT9D,_DONE)") (class "Default")
      (node (ref "P2") (pin "13") (pinfunction "13_13") (pintype "passive"))
      (node (ref "U3") (pin "76") (pinfunction "PT9D,_DONE_76") (pintype "bidirectional"))
    )
    (net (code "40") (name "Net-(U3B-PR2A)") (class "Default")
      (node (ref "P3") (pin "1") (pinfunction "1_1") (pintype "passive"))
      (node (ref "U3") (pin "75") (pinfunction "PR2A_75") (pintype "bidirectional"))
    )
    (net (code "41") (name "Net-(U3B-PR2B)") (class "Default")
      (node (ref "P3") (pin "2") (pinfunction "2_2") (pintype "passive"))
      (node (ref "U3") (pin "74") (pinfunction "PR2B_74") (pintype "bidirectional"))
    )
    (net (code "42") (name "Net-(U3B-PR3A)") (class "Default")
      (node (ref "P3") (pin "3") (pinfunction "3_3") (pintype "passive"))
      (node (ref "U3") (pin "71") (pinfunction "PR3A_71") (pintype "bidirectional"))
    )
    (net (code "43") (name "Net-(U3B-PR3B)") (class "Default")
      (node (ref "P3") (pin "4") (pinfunction "4_4") (pintype "passive"))
      (node (ref "U3") (pin "70") (pinfunction "PR3B_70") (pintype "bidirectional"))
    )
    (net (code "44") (name "Net-(U3B-PR3C)") (class "Default")
      (node (ref "P3") (pin "5") (pinfunction "5_5") (pintype "passive"))
      (node (ref "U3") (pin "67") (pinfunction "PR3C_67") (pintype "bidirectional"))
    )
    (net (code "45") (name "Net-(U3B-PR3D)") (class "Default")
      (node (ref "P3") (pin "6") (pinfunction "6_6") (pintype "passive"))
      (node (ref "U3") (pin "66") (pinfunction "PR3D_66") (pintype "bidirectional"))
    )
    (net (code "46") (name "Net-(U3B-PR5C)") (class "Default")
      (node (ref "P3") (pin "7") (pinfunction "7_7") (pintype "passive"))
      (node (ref "U3") (pin "58") (pinfunction "PR5C_58") (pintype "bidirectional"))
    )
    (net (code "47") (name "Net-(U3B-PR5D)") (class "Default")
      (node (ref "P3") (pin "8") (pinfunction "8_8") (pintype "passive"))
      (node (ref "U3") (pin "57") (pinfunction "PR5D_57") (pintype "bidirectional"))
    )
    (net (code "48") (name "Net-(U3B-PR6A)") (class "Default")
      (node (ref "P3") (pin "9") (pinfunction "9_9") (pintype "passive"))
      (node (ref "U3") (pin "54") (pinfunction "PR6A_54") (pintype "bidirectional"))
    )
    (net (code "49") (name "Net-(U3B-PR6B)") (class "Default")
      (node (ref "P3") (pin "10") (pinfunction "10_10") (pintype "passive"))
      (node (ref "U3") (pin "53") (pinfunction "PR6B_53") (pintype "bidirectional"))
    )
    (net (code "50") (name "Net-(U3B-PR6C)") (class "Default")
      (node (ref "P3") (pin "11") (pinfunction "11_11") (pintype "passive"))
      (node (ref "U3") (pin "52") (pinfunction "PR6C_52") (pintype "bidirectional"))
    )
    (net (code "51") (name "Net-(U3B-PR6D)") (class "Default")
      (node (ref "R13") (pin "1") (pinfunction "1_1") (pintype "passive"))
      (node (ref "R14") (pin "1") (pinfunction "1_1") (pintype "passive"))
      (node (ref "U3") (pin "51") (pinfunction "PR6D_51") (pintype "bidirectional"))
    )
    (net (code "52") (name "Net-(U3C-PB2A,_CSSPIN)") (class "Default")
      (node (ref "P2") (pin "10") (pinfunction "10_10") (pintype "passive"))
      (node (ref "U3") (pin "27") (pinfunction "PB2A,_CSSPIN_27") (pintype "bidirectional"))
    )
    (net (code "53") (name "Net-(U3C-PB2C,_MCLK{slash}CCLK)") (class "Default")
      (node (ref "P2") (pin "9") (pinfunction "9_9") (pintype "passive"))
      (node (ref "U3") (pin "31") (pinfunction "PB2C,_MCLK/CCLK_31") (pintype "bidirectional"))
    )
    (net (code "54") (name "Net-(U3C-PB2D,_SO{slash}SPISO)") (class "Default")
      (node (ref "P2") (pin "8") (pinfunction "8_8") (pintype "passive"))
      (node (ref "U3") (pin "32") (pinfunction "PB2D,_SO/SPISO_32") (pintype "bidirectional"))
    )
    (net (code "55") (name "Net-(U3C-PB9A,_SN)") (class "Default")
      (node (ref "P2") (pin "12") (pinfunction "12_12") (pintype "passive"))
      (node (ref "U3") (pin "48") (pinfunction "PB9A,_SN_48") (pintype "bidirectional"))
    )
    (net (code "56") (name "Net-(U3C-PB9B,_SI{slash}SISPI)") (class "Default")
      (node (ref "P2") (pin "11") (pinfunction "11_11") (pintype "passive"))
      (node (ref "U3") (pin "49") (pinfunction "PB9B,_SI/SISPI_49") (pintype "bidirectional"))
    )
    (net (code "57") (name "VBUS") (class "Default")
      (node (ref "C1") (pin "1") (pinfunction "1_1") (pintype "passive"))
      (node (ref "C5") (pin "2") (pinfunction "2_2") (pintype "passive"))
      (node (ref "C6") (pin "2") (pinfunction "2_2") (pintype "passive"))
      (node (ref "FB1") (pin "1") (pinfunction "1_1") (pintype "passive"))
      (node (ref "U1") (pin "7") (pinfunction "VREGIN_7") (pintype "power_in"))
      (node (ref "U1") (pin "8") (pinfunction "VBUS_8") (pintype "power_in"))
    )
    (net (code "58") (name "VBUS_IN") (class "Default")
      (node (ref "D1") (pin "4") (pinfunction "4_4") (pintype "passive"))
      (node (ref "FB1") (pin "2") (pinfunction "2_2") (pintype "passive"))
      (node (ref "J1") (pin "1") (pinfunction "VBUS_1") (pintype "passive"))
    )
    (net (code "59") (name "VCCIO0") (class "Default")
      (node (ref "C10") (pin "1") (pinfunction "1_1") (pintype "passive"))
      (node (ref "C11") (pin "1") (pinfunction "1_1") (pintype "passive"))
      (node (ref "C9") (pin "1") (pinfunction "1_1") (pintype "passive"))
      (node (ref "R9") (pin "1") (pinfunction "1_1") (pintype "passive"))
      (node (ref "U3") (pin "80") (pinfunction "VCCIO0_80") (pintype "power_in"))
      (node (ref "U3") (pin "93") (pinfunction "VCCIO0_93") (pintype "power_in"))
    )
    (net (code "60") (name "VCCIO1") (class "Default")
      (node (ref "C16") (pin "1") (pinfunction "1_1") (pintype "passive"))
      (node (ref "C17") (pin "1") (pinfunction "1_1") (pintype "passive"))
      (node (ref "C18") (pin "1") (pinfunction "1_1") (pintype "passive"))
      (node (ref "R10") (pin "1") (pinfunction "1_1") (pintype "passive"))
      (node (ref "U3") (pin "55") (pinfunction "VCCIO1_55") (pintype "power_in"))
      (node (ref "U3") (pin "73") (pinfunction "VCCIO1_73") (pintype "power_in"))
    )
    (net (code "61") (name "VCCIO2") (class "Default")
      (node (ref "C25") (pin "1") (pinfunction "1_1") (pintype "passive"))
      (node (ref "C26") (pin "1") (pinfunction "1_1") (pintype "passive"))
      (node (ref "C27") (pin "1") (pinfunction "1_1") (pintype "passive"))
      (node (ref "R11") (pin "1") (pinfunction "1_1") (pintype "passive"))
      (node (ref "U3") (pin "26") (pinfunction "VCCIO2_26") (pintype "power_in"))
      (node (ref "U3") (pin "46") (pinfunction "VCCIO2_46") (pintype "power_in"))
    )
    (net (code "62") (name "VCCIO3") (class "Default")
      (node (ref "C21") (pin "1") (pinfunction "1_1") (pintype "passive"))
      (node (ref "C22") (pin "1") (pinfunction "1_1") (pintype "passive"))
      (node (ref "C23") (pin "1") (pinfunction "1_1") (pintype "passive"))
      (node (ref "C24") (pin "1") (pinfunction "1_1") (pintype "passive"))
      (node (ref "R12") (pin "1") (pinfunction "1_1") (pintype "passive"))
      (node (ref "U3") (pin "11") (pinfunction "VCCIO3_11") (pintype "power_in"))
      (node (ref "U3") (pin "23") (pinfunction "VCCIO3_23") (pintype "power_in"))
      (node (ref "U3") (pin "5") (pinfunction "VCCIO3_5") (pintype "power_in"))
    )
    (net (code "63") (name "unconnected-(J1-ID-Pad4)") (class "Default")
      (node (ref "J1") (pin "4") (pinfunction "ID_4") (pintype "passive"))
    )
    (net (code "64") (name "unconnected-(J2-Pad5)") (class "Default")
      (node (ref "J2") (pin "5") (pinfunction "5_5") (pintype "passive"))
    )
    (net (code "65") (name "unconnected-(M1-NC-Pad16)") (class "Default")
      (node (ref "M1") (pin "16") (pinfunction "NC_16") (pintype "passive+no_connect"))
    )
    (net (code "66") (name "unconnected-(M1-NC-Pad17)") (class "Default")
      (node (ref "M1") (pin "17") (pinfunction "NC_17") (pintype "passive+no_connect"))
    )
    (net (code "67") (name "unconnected-(SW1-Pad1)") (class "Default")
      (node (ref "SW1") (pin "1") (pinfunction "1_1") (pintype "passive+no_connect"))
    )
    (net (code "68") (name "unconnected-(SW1-Pad2)") (class "Default")
      (node (ref "SW1") (pin "2") (pinfunction "2_2") (pintype "passive+no_connect"))
    )
    (net (code "69") (name "unconnected-(U1-GPIO.2{slash}RS485-Pad12)") (class "Default")
      (node (ref "U1") (pin "12") (pinfunction "GPIO.2/RS485_12") (pintype "bidirectional+no_connect"))
    )
    (net (code "70") (name "unconnected-(U1-GPIO.3{slash}WAKEUP-Pad11)") (class "Default")
      (node (ref "U1") (pin "11") (pinfunction "GPIO.3/WAKEUP_11") (pintype "bidirectional+no_connect"))
    )
    (net (code "71") (name "unconnected-(U1-NC-Pad10)") (class "Default")
      (node (ref "U1") (pin "10") (pinfunction "NC_10") (pintype "passive+no_connect"))
    )
    (net (code "72") (name "unconnected-(U1-NC-Pad16)") (class "Default")
      (node (ref "U1") (pin "16") (pinfunction "NC_16") (pintype "passive+no_connect"))
    )
    (net (code "73") (name "unconnected-(U1-SUSPEND-Pad17)") (class "Default")
      (node (ref "U1") (pin "17") (pinfunction "SUSPEND_17") (pintype "output+no_connect"))
    )
    (net (code "74") (name "unconnected-(U1-~{CTS}-Pad18)") (class "Default")
      (node (ref "U1") (pin "18") (pinfunction "~{CTS}_18") (pintype "input+no_connect"))
    )
    (net (code "75") (name "unconnected-(U1-~{DCD}-Pad24)") (class "Default")
      (node (ref "U1") (pin "24") (pinfunction "~{DCD}_24") (pintype "input+no_connect"))
    )
    (net (code "76") (name "unconnected-(U1-~{DSR}-Pad22)") (class "Default")
      (node (ref "U1") (pin "22") (pinfunction "~{DSR}_22") (pintype "input+no_connect"))
    )
    (net (code "77") (name "unconnected-(U1-~{DTR}-Pad23)") (class "Default")
      (node (ref "U1") (pin "23") (pinfunction "~{DTR}_23") (pintype "output+no_connect"))
    )
    (net (code "78") (name "unconnected-(U1-~{RI}{slash}CLK-Pad1)") (class "Default")
      (node (ref "U1") (pin "1") (pinfunction "~{RI}/CLK_1") (pintype "bidirectional+no_connect"))
    )
    (net (code "79") (name "unconnected-(U1-~{RTS}-Pad19)") (class "Default")
      (node (ref "U1") (pin "19") (pinfunction "~{RTS}_19") (pintype "output+no_connect"))
    )
    (net (code "80") (name "unconnected-(U3A-PT6A-Pad99)") (class "Default")
      (node (ref "U3") (pin "99") (pinfunction "PT6A_99") (pintype "bidirectional+no_connect"))
    )
    (net (code "81") (name "unconnected-(U3A-PT6B-Pad98)") (class "Default")
      (node (ref "U3") (pin "98") (pinfunction "PT6B_98") (pintype "bidirectional+no_connect"))
    )
    (net (code "82") (name "unconnected-(U3A-PT8A,_PCLKT0_1-Pad88)") (class "Default")
      (node (ref "U3") (pin "88") (pinfunction "PT8A,_PCLKT0_1_88") (pintype "bidirectional+no_connect"))
    )
    (net (code "83") (name "unconnected-(U3A-PT8B,_PCLKC0_1-Pad87)") (class "Default")
      (node (ref "U3") (pin "87") (pinfunction "PT8B,_PCLKC0_1_87") (pintype "bidirectional+no_connect"))
    )
    (net (code "84") (name "unconnected-(U3A-PT8C,_SCL{slash}PCLKT0_0-Pad86)") (class "Default")
      (node (ref "U3") (pin "86") (pinfunction "PT8C,_SCL/PCLKT0_0_86") (pintype "bidirectional+no_connect"))
    )
    (net (code "85") (name "unconnected-(U3A-PT8D,_SDA{slash}PCLKC0_0-Pad85)") (class "Default")
      (node (ref "U3") (pin "85") (pinfunction "PT8D,_SDA/PCLKC0_0_85") (pintype "bidirectional+no_connect"))
    )
    (net (code "86") (name "unconnected-(U3B-PR5A,_PCLKT1_0-Pad63)") (class "Default")
      (node (ref "U3") (pin "63") (pinfunction "PR5A,_PCLKT1_0_63") (pintype "bidirectional+no_connect"))
    )
    (net (code "87") (name "unconnected-(U3B-PR5B,_PCLKC1_0-Pad62)") (class "Default")
      (node (ref "U3") (pin "62") (pinfunction "PR5B,_PCLKC1_0_62") (pintype "bidirectional+no_connect"))
    )
    (net (code "88") (name "unconnected-(U3C-PB2B-Pad28)") (class "Default")
      (node (ref "U3") (pin "28") (pinfunction "PB2B_28") (pintype "bidirectional+no_connect"))
    )
    (net (code "89") (name "unconnected-(U3C-PB4A,_PCLKT2_0-Pad34)") (class "Default")
      (node (ref "U3") (pin "34") (pinfunction "PB4A,_PCLKT2_0_34") (pintype "bidirectional+no_connect"))
    )
    (net (code "90") (name "unconnected-(U3C-PB4B,_PCLKC2_0-Pad35)") (class "Default")
      (node (ref "U3") (pin "35") (pinfunction "PB4B,_PCLKC2_0_35") (pintype "bidirectional+no_connect"))
    )
    (net (code "91") (name "unconnected-(U3C-PB4C,_PCLKT2_1-Pad38)") (class "Default")
      (node (ref "U3") (pin "38") (pinfunction "PB4C,_PCLKT2_1_38") (pintype "bidirectional+no_connect"))
    )
    (net (code "92") (name "unconnected-(U3C-PB4D,_PCLKC2_1-Pad39)") (class "Default")
      (node (ref "U3") (pin "39") (pinfunction "PB4D,_PCLKC2_1_39") (pintype "bidirectional+no_connect"))
    )
    (net (code "93") (name "unconnected-(U3C-PB7A-Pad40)") (class "Default")
      (node (ref "U3") (pin "40") (pinfunction "PB7A_40") (pintype "bidirectional+no_connect"))
    )
    (net (code "94") (name "unconnected-(U3C-PB7B-Pad41)") (class "Default")
      (node (ref "U3") (pin "41") (pinfunction "PB7B_41") (pintype "bidirectional+no_connect"))
    )
    (net (code "95") (name "unconnected-(U3C-PB7C-Pad42)") (class "Default")
      (node (ref "U3") (pin "42") (pinfunction "PB7C_42") (pintype "bidirectional+no_connect"))
    )
    (net (code "96") (name "unconnected-(U3C-PB7D-Pad43)") (class "Default")
      (node (ref "U3") (pin "43") (pinfunction "PB7D_43") (pintype "bidirectional+no_connect"))
    )
    (net (code "97") (name "unconnected-(U3D-PL2A-Pad1)") (class "Default")
      (node (ref "U3") (pin "1") (pinfunction "PL2A_1") (pintype "bidirectional+no_connect"))
    )
    (net (code "98") (name "unconnected-(U3D-PL2B-Pad2)") (class "Default")
      (node (ref "U3") (pin "2") (pinfunction "PL2B_2") (pintype "bidirectional+no_connect"))
    )
    (net (code "99") (name "unconnected-(U3D-PL2C,_PCLKT3_2-Pad3)") (class "Default")
      (node (ref "U3") (pin "3") (pinfunction "PL2C,_PCLKT3_2_3") (pintype "bidirectional+no_connect"))
    )
    (net (code "100") (name "unconnected-(U3D-PL2D,_PCLKC3_2-Pad4)") (class "Default")
      (node (ref "U3") (pin "4") (pinfunction "PL2D,_PCLKC3_2_4") (pintype "bidirectional+no_connect"))
    )
    (net (code "101") (name "unconnected-(U3D-PL3A-Pad7)") (class "Default")
      (node (ref "U3") (pin "7") (pinfunction "PL3A_7") (pintype "bidirectional+no_connect"))
    )
    (net (code "102") (name "unconnected-(U3D-PL3B-Pad8)") (class "Default")
      (node (ref "U3") (pin "8") (pinfunction "PL3B_8") (pintype "bidirectional+no_connect"))
    )
    (net (code "103") (name "unconnected-(U3D-PL3C,_PCLKT3_1-Pad12)") (class "Default")
      (node (ref "U3") (pin "12") (pinfunction "PL3C,_PCLKT3_1_12") (pintype "bidirectional+no_connect"))
    )
    (net (code "104") (name "unconnected-(U3D-PL3D,_PCLKC3_1-Pad13)") (class "Default")
      (node (ref "U3") (pin "13") (pinfunction "PL3D,_PCLKC3_1_13") (pintype "bidirectional+no_connect"))
    )
    (net (code "105") (name "unconnected-(U3D-PL5A-Pad16)") (class "Default")
      (node (ref "U3") (pin "16") (pinfunction "PL5A_16") (pintype "bidirectional+no_connect"))
    )
    (net (code "106") (name "unconnected-(U3D-PL5B-Pad17)") (class "Default")
      (node (ref "U3") (pin "17") (pinfunction "PL5B_17") (pintype "bidirectional+no_connect"))
    )
    (net (code "107") (name "unconnected-(U3D-PL5C,_PCLKT3_0-Pad20)") (class "Default")
      (node (ref "U3") (pin "20") (pinfunction "PL5C,_PCLKT3_0_20") (pintype "bidirectional+no_connect"))
    )
    (net (code "108") (name "unconnected-(U3D-PL5D,_PCLKC3_0-Pad21)") (class "Default")
      (node (ref "U3") (pin "21") (pinfunction "PL5D,_PCLKC3_0_21") (pintype "bidirectional+no_connect"))
    )
    (net (code "109") (name "unconnected-(U3D-PL6A-Pad24)") (class "Default")
      (node (ref "U3") (pin "24") (pinfunction "PL6A_24") (pintype "bidirectional+no_connect"))
    )
    (net (code "110") (name "unconnected-(U3D-PL6B-Pad25)") (class "Default")
      (node (ref "U3") (pin "25") (pinfunction "PL6B_25") (pintype "bidirectional+no_connect"))
    )
    (net (code "111") (name "unconnected-(U3E-VCCP-Pad89)") (class "Default")
      (node (ref "U3") (pin "89") (pinfunction "VCCP_89") (pintype "power_in"))
    )
    (net (code "112") (name "unconnected-(U3G-NC-Pad9)") (class "Default")
      (node (ref "U3") (pin "9") (pinfunction "NC_9") (pintype "passive+no_connect"))
    )
    (net (code "113") (name "unconnected-(U3G-NC-Pad10)") (class "Default")
      (node (ref "U3") (pin "10") (pinfunction "NC_10") (pintype "passive+no_connect"))
    )
    (net (code "114") (name "unconnected-(U3G-NC-Pad14)") (class "Default")
      (node (ref "U3") (pin "14") (pinfunction "NC_14") (pintype "passive+no_connect"))
    )
    (net (code "115") (name "unconnected-(U3G-NC-Pad15)") (class "Default")
      (node (ref "U3") (pin "15") (pinfunction "NC_15") (pintype "passive+no_connect"))
    )
    (net (code "116") (name "unconnected-(U3G-NC-Pad18)") (class "Default")
      (node (ref "U3") (pin "18") (pinfunction "NC_18") (pintype "passive+no_connect"))
    )
    (net (code "117") (name "unconnected-(U3G-NC-Pad19)") (class "Default")
      (node (ref "U3") (pin "19") (pinfunction "NC_19") (pintype "passive+no_connect"))
    )
    (net (code "118") (name "unconnected-(U3G-NC-Pad29)") (class "Default")
      (node (ref "U3") (pin "29") (pinfunction "NC_29") (pintype "passive+no_connect"))
    )
    (net (code "119") (name "unconnected-(U3G-NC-Pad30)") (class "Default")
      (node (ref "U3") (pin "30") (pinfunction "NC_30") (pintype "passive+no_connect"))
    )
    (net (code "120") (name "unconnected-(U3G-NC-Pad36)") (class "Default")
      (node (ref "U3") (pin "36") (pinfunction "NC_36") (pintype "passive+no_connect"))
    )
    (net (code "121") (name "unconnected-(U3G-NC-Pad37)") (class "Default")
      (node (ref "U3") (pin "37") (pinfunction "NC_37") (pintype "passive+no_connect"))
    )
    (net (code "122") (name "unconnected-(U3G-NC-Pad45)") (class "Default")
      (node (ref "U3") (pin "45") (pinfunction "NC_45") (pintype "passive+no_connect"))
    )
    (net (code "123") (name "unconnected-(U3G-NC-Pad47)") (class "Default")
      (node (ref "U3") (pin "47") (pinfunction "NC_47") (pintype "passive+no_connect"))
    )
    (net (code "124") (name "unconnected-(U3G-NC-Pad59)") (class "Default")
      (node (ref "U3") (pin "59") (pinfunction "NC_59") (pintype "passive+no_connect"))
    )
    (net (code "125") (name "unconnected-(U3G-NC-Pad60)") (class "Default")
      (node (ref "U3") (pin "60") (pinfunction "NC_60") (pintype "passive+no_connect"))
    )
    (net (code "126") (name "unconnected-(U3G-NC-Pad61)") (class "Default")
      (node (ref "U3") (pin "61") (pinfunction "NC_61") (pintype "passive+no_connect"))
    )
    (net (code "127") (name "unconnected-(U3G-NC-Pad64)") (class "Default")
      (node (ref "U3") (pin "64") (pinfunction "NC_64") (pintype "passive+no_connect"))
    )
    (net (code "128") (name "unconnected-(U3G-NC-Pad65)") (class "Default")
      (node (ref "U3") (pin "65") (pinfunction "NC_65") (pintype "passive+no_connect"))
    )
    (net (code "129") (name "unconnected-(U3G-NC-Pad68)") (class "Default")
      (node (ref "U3") (pin "68") (pinfunction "NC_68") (pintype "passive+no_connect"))
    )
    (net (code "130") (name "unconnected-(U3G-NC-Pad69)") (class "Default")
      (node (ref "U3") (pin "69") (pinfunction "NC_69") (pintype "passive+no_connect"))
    )
    (net (code "131") (name "unconnected-(U3G-NC-Pad78)") (class "Default")
      (node (ref "U3") (pin "78") (pinfunction "NC_78") (pintype "passive+no_connect"))
    )
    (net (code "132") (name "unconnected-(U3G-NC-Pad83)") (class "Default")
      (node (ref "U3") (pin "83") (pinfunction "NC_83") (pintype "passive+no_connect"))
    )
    (net (code "133") (name "unconnected-(U3G-NC-Pad84)") (class "Default")
      (node (ref "U3") (pin "84") (pinfunction "NC_84") (pintype "passive+no_connect"))
    )
    (net (code "134") (name "unconnected-(U3G-NC-Pad96)") (class "Default")
      (node (ref "U3") (pin "96") (pinfunction "NC_96") (pintype "passive+no_connect"))
    )
    (net (code "135") (name "unconnected-(U3G-NC-Pad97)") (class "Default")
      (node (ref "U3") (pin "97") (pinfunction "NC_97") (pintype "passive+no_connect"))
    )
  )
)
